# lora_internal_dev_board.net
KiCad netlist of a schematic drawn in EasyEDA
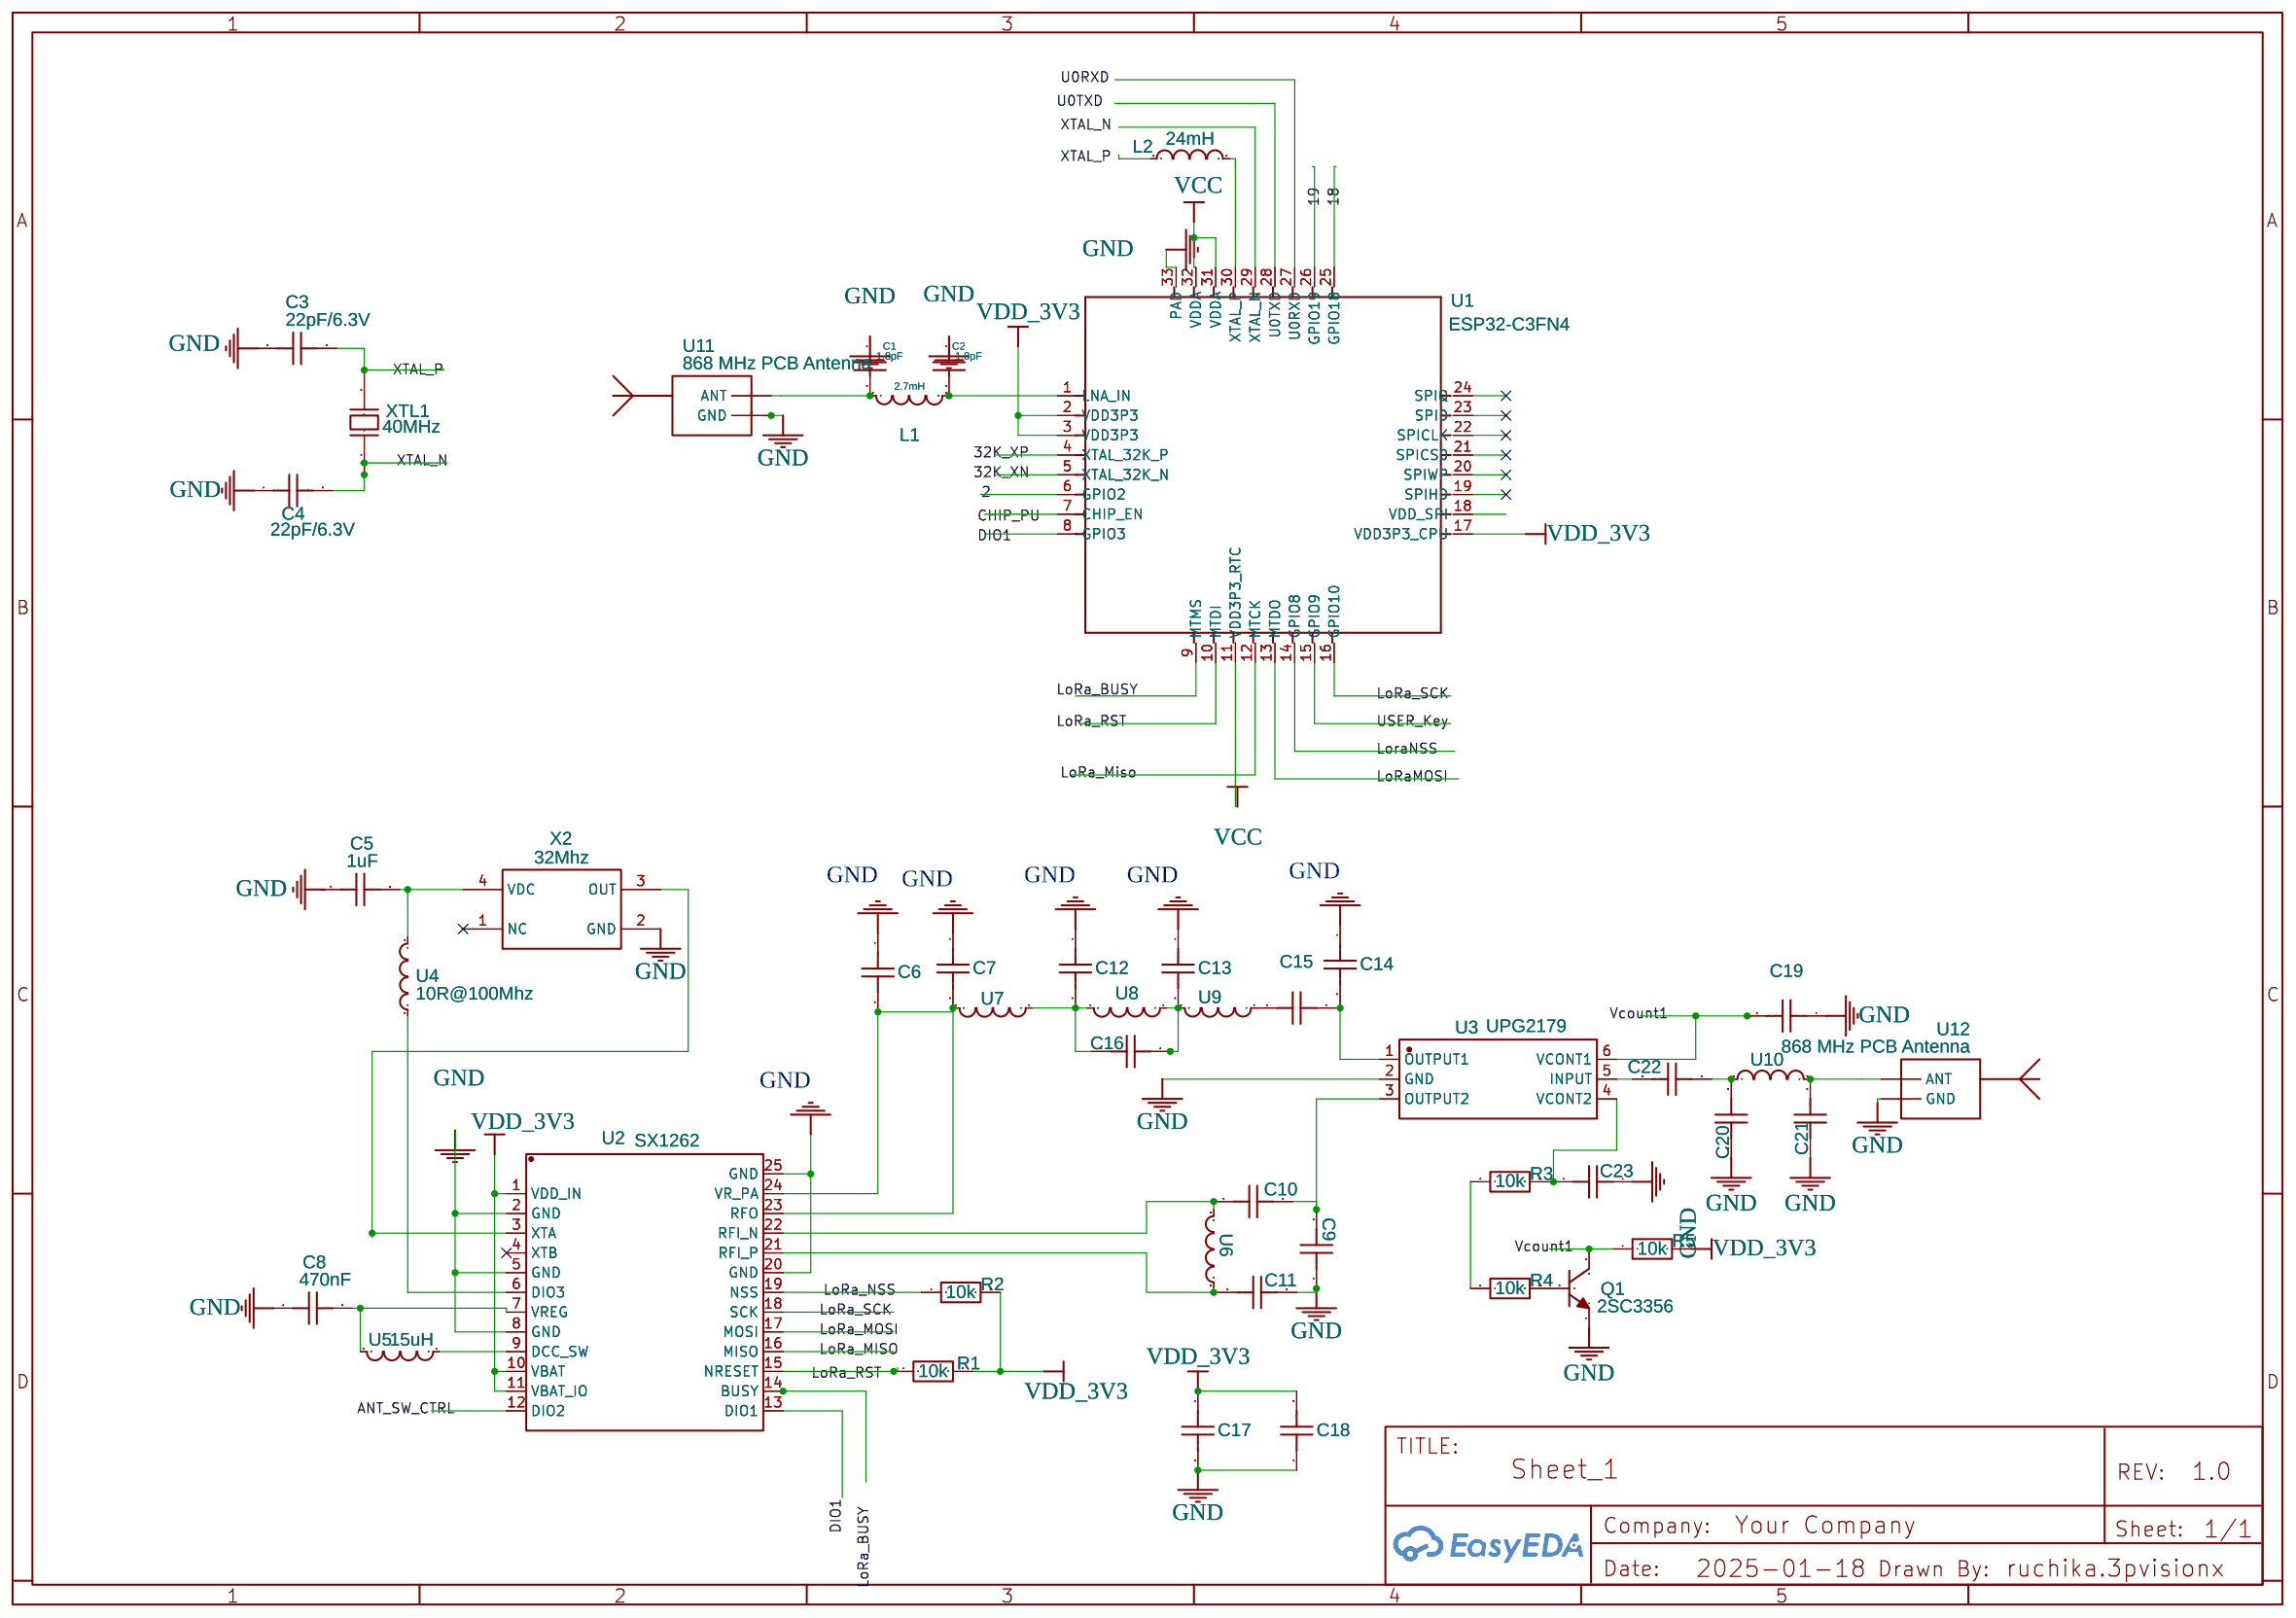
[diagram p0: schematic sheet]

(export (version "E")
  (design (tool "Eeschema 10.0.6"))
  (components
    (comp (ref "C1")
      (value "1.8pF")
      (fields
        (field (name "Manufacturer Part") "GJM1555C1H1R8BB01D")
        (field (name "Manufacturer") "muRata(村田)")
      )
      (libsource (lib "") (part "GJM1555C1H1R8BB01D"))
    )
    (comp (ref "C2")
      (value "1.8pF")
      (fields
        (field (name "Manufacturer Part") "GJM1555C1H1R8BB01D")
        (field (name "Manufacturer") "muRata(村田)")
      )
      (libsource (lib "") (part "GJM1555C1H1R8BB01D"))
    )
    (comp (ref "C3")
      (value "22pF/6.3V")
      (fields (field (name "Manufacturer Part") "22pF/6.3V(10%)-0402"))
      (libsource (lib "") (part "22PF/6.3V(10%)-0402"))
    )
    (comp (ref "C4")
      (value "22pF/6.3V")
      (fields (field (name "Manufacturer Part") "22pF/6.3V(10%)-0402"))
      (libsource (lib "") (part "22PF/6.3V(10%)-0402"))
    )
    (comp (ref "C5")
      (value "1uF")
      (fields
        (field (name "Manufacturer Part") "1uf/250V/CBBCapacitor")
        (field (name "Manufacturer") "ReliaPro")
      )
      (libsource (lib "") (part "1uf/250V/CBBCapacitor_3"))
    )
    (comp (ref "C6")
      (value "1uF")
      (fields
        (field (name "Manufacturer Part") "1uf/250V/CBBCapacitor")
        (field (name "Manufacturer") "ReliaPro")
      )
      (libsource (lib "") (part "1uf/250V/CBBCapacitor"))
    )
    (comp (ref "C7")
      (value "1uF")
      (fields
        (field (name "Manufacturer Part") "1uf/250V/CBBCapacitor")
        (field (name "Manufacturer") "ReliaPro")
      )
      (libsource (lib "") (part "1uf/250V/CBBCapacitor"))
    )
    (comp (ref "C8")
      (value "470nF")
      (fields
        (field (name "Manufacturer Part") "1uf/250V/CBBCapacitor")
        (field (name "Manufacturer") "ReliaPro")
      )
      (libsource (lib "") (part "1uf/250V/CBBCapacitor_3"))
    )
    (comp (ref "C9")
      (value "1uF")
      (fields
        (field (name "Manufacturer Part") "1uf/250V/CBBCapacitor")
        (field (name "Manufacturer") "ReliaPro")
      )
      (libsource (lib "") (part "1uf/250V/CBBCapacitor_2"))
    )
    (comp (ref "C10")
      (value "1uF")
      (fields
        (field (name "Manufacturer Part") "1uf/250V/CBBCapacitor")
        (field (name "Manufacturer") "ReliaPro")
      )
      (libsource (lib "") (part "1uf/250V/CBBCapacitor_3"))
    )
    (comp (ref "C11")
      (value "1uF")
      (fields
        (field (name "Manufacturer Part") "1uf/250V/CBBCapacitor")
        (field (name "Manufacturer") "ReliaPro")
      )
      (libsource (lib "") (part "1uf/250V/CBBCapacitor_3"))
    )
    (comp (ref "C12")
      (value "1uF")
      (fields
        (field (name "Manufacturer Part") "1uf/250V/CBBCapacitor")
        (field (name "Manufacturer") "ReliaPro")
      )
      (libsource (lib "") (part "1uf/250V/CBBCapacitor"))
    )
    (comp (ref "C13")
      (value "1uF")
      (fields
        (field (name "Manufacturer Part") "1uf/250V/CBBCapacitor")
        (field (name "Manufacturer") "ReliaPro")
      )
      (libsource (lib "") (part "1uf/250V/CBBCapacitor"))
    )
    (comp (ref "C14")
      (value "1uF")
      (fields
        (field (name "Manufacturer Part") "1uf/250V/CBBCapacitor")
        (field (name "Manufacturer") "ReliaPro")
      )
      (libsource (lib "") (part "1uf/250V/CBBCapacitor"))
    )
    (comp (ref "C15")
      (value "1uF")
      (fields
        (field (name "Manufacturer Part") "1uf/250V/CBBCapacitor")
        (field (name "Manufacturer") "ReliaPro")
      )
      (libsource (lib "") (part "1uf/250V/CBBCapacitor_1"))
    )
    (comp (ref "C16")
      (value "1uF")
      (fields
        (field (name "Manufacturer Part") "1uf/250V/CBBCapacitor")
        (field (name "Manufacturer") "ReliaPro")
      )
      (libsource (lib "") (part "1uf/250V/CBBCapacitor_1"))
    )
    (comp (ref "C17")
      (value "1uF")
      (fields
        (field (name "Manufacturer Part") "1uf/250V/CBBCapacitor")
        (field (name "Manufacturer") "ReliaPro")
      )
      (libsource (lib "") (part "1uf/250V/CBBCapacitor"))
    )
    (comp (ref "C18")
      (value "1uF")
      (fields
        (field (name "Manufacturer Part") "1uf/250V/CBBCapacitor")
        (field (name "Manufacturer") "ReliaPro")
      )
      (libsource (lib "") (part "1uf/250V/CBBCapacitor_2"))
    )
    (comp (ref "C19")
      (value "1uF")
      (fields
        (field (name "Manufacturer Part") "1uf/250V/CBBCapacitor")
        (field (name "Manufacturer") "ReliaPro")
      )
      (libsource (lib "") (part "1uf/250V/CBBCapacitor_1"))
    )
    (comp (ref "C20")
      (value "1uF")
      (fields
        (field (name "Manufacturer Part") "1uf/250V/CBBCapacitor")
        (field (name "Manufacturer") "ReliaPro")
      )
      (libsource (lib "") (part "1uf/250V/CBBCapacitor_2"))
    )
    (comp (ref "C21")
      (value "1uF")
      (fields
        (field (name "Manufacturer Part") "1uf/250V/CBBCapacitor")
        (field (name "Manufacturer") "ReliaPro")
      )
      (libsource (lib "") (part "1uf/250V/CBBCapacitor_2"))
    )
    (comp (ref "C22")
      (value "1uF")
      (fields
        (field (name "Manufacturer Part") "1uf/250V/CBBCapacitor")
        (field (name "Manufacturer") "ReliaPro")
      )
      (libsource (lib "") (part "1uf/250V/CBBCapacitor_1"))
    )
    (comp (ref "C23")
      (value "1uF")
      (fields
        (field (name "Manufacturer Part") "1uf/250V/CBBCapacitor")
        (field (name "Manufacturer") "ReliaPro")
      )
      (libsource (lib "") (part "1uf/250V/CBBCapacitor_1"))
    )
    (comp (ref "L1") (value "2.7mH") (libsource (lib "") (part "2.7mH sb3m")))
    (comp (ref "L2")
      (value "24mH")
      (fields (field (name "Manufacturer") "ML"))
      (libsource (lib "") (part "Inductor TH"))
    )
    (comp (ref "Q1")
      (value "2SC3356")
      (fields (field (name "Manufacturer") "FOSAN(富信)"))
      (libsource (lib "") (part "2SC3356_C5119709"))
    )
    (comp (ref "R1")
      (value "10k")
      (fields (field (name "Manufacturer Part") "贴片电阻ChipResistors"))
      (libsource (lib "") (part "贴片电阻CHIPRESISTORS"))
    )
    (comp (ref "R2")
      (value "10k")
      (fields (field (name "Manufacturer Part") "贴片电阻ChipResistors"))
      (libsource (lib "") (part "贴片电阻CHIPRESISTORS"))
    )
    (comp (ref "R3")
      (value "10k")
      (fields (field (name "Manufacturer Part") "贴片电阻ChipResistors"))
      (libsource (lib "") (part "贴片电阻CHIPRESISTORS"))
    )
    (comp (ref "R4")
      (value "10k")
      (fields (field (name "Manufacturer Part") "贴片电阻ChipResistors"))
      (libsource (lib "") (part "贴片电阻CHIPRESISTORS"))
    )
    (comp (ref "R5")
      (value "10k")
      (fields (field (name "Manufacturer Part") "贴片电阻ChipResistors"))
      (libsource (lib "") (part "贴片电阻CHIPRESISTORS"))
    )
    (comp (ref "U1") (value "ESP32-C3FN4") (libsource (lib "") (part "ESP32-C3FN4")))
    (comp (ref "U2")
      (value "SX1262")
      (fields (field (name "Manufacturer Part") "SX1262IMLTRT") (field (name "Manufacturer") "SEMTECH"))
      (libsource (lib "") (part "SX1262IMLTRT"))
    )
    (comp (ref "U3")
      (value "UPG2179")
      (fields
        (field (name "Manufacturer Part") "UPG2179TB-E4-A")
        (field (name "Manufacturer") "RENESAS(瑞萨)/IDT")
      )
      (libsource (lib "") (part "UPG2179TB-E4-A"))
    )
    (comp (ref "U4")
      (value "10R@100Mhz")
      (fields (field (name "Manufacturer Part") "10uH-INDUCTOR-0603"))
      (libsource (lib "") (part "10UH-INDUCTOR-0603"))
    )
    (comp (ref "U5")
      (value "15uH")
      (fields (field (name "Manufacturer Part") "10uH-INDUCTOR-0603"))
      (libsource (lib "") (part "10UH-INDUCTOR-0603_3"))
    )
    (comp (ref "U6")
      (value "15uH")
      (fields (field (name "Manufacturer Part") "10uH-INDUCTOR-0603"))
      (libsource (lib "") (part "10UH-INDUCTOR-0603_2"))
    )
    (comp (ref "U7")
      (value "15uH")
      (fields (field (name "Manufacturer Part") "10uH-INDUCTOR-0603"))
      (libsource (lib "") (part "10UH-INDUCTOR-0603_5"))
    )
    (comp (ref "U8")
      (value "15uH")
      (fields (field (name "Manufacturer Part") "10uH-INDUCTOR-0603"))
      (libsource (lib "") (part "10UH-INDUCTOR-0603_5"))
    )
    (comp (ref "U9")
      (value "15uH")
      (fields (field (name "Manufacturer Part") "10uH-INDUCTOR-0603"))
      (libsource (lib "") (part "10UH-INDUCTOR-0603_4"))
    )
    (comp (ref "U10")
      (value "15uH")
      (fields (field (name "Manufacturer Part") "10uH-INDUCTOR-0603"))
      (libsource (lib "") (part "10UH-INDUCTOR-0603_1"))
    )
    (comp (ref "U11") (value "868 MHz PCB Antenna") (libsource (lib "") (part "868 MHz PCB Antenna")))
    (comp (ref "U12") (value "868 MHz PCB Antenna") (libsource (lib "") (part "868 MHz PCB Antenna_1")))
    (comp (ref "X2")
      (value "32Mhz")
      (fields (field (name "Manufacturer") "YIC"))
      (libsource (lib "") (part "OSC40M-3.3/S5"))
    )
    (comp (ref "XTL1")
      (value "40MHz")
      (fields (field (name "Manufacturer Part") "NTPL INSIDE"))
      (libsource (lib "") (part "XTL - 16MHZ"))
    )
  )
  (nets
    (net (code "1") (name "/2") (class "Default")
      (node (ref "U1") (pin "6") (pinfunction "GPIO2_6") (pintype "unspecified"))
    )
    (net (code "9") (name "/LoRaMOSI") (class "Default")
      (node (ref "U1") (pin "13") (pinfunction "MTDO_13") (pintype "unspecified"))
    )
    (net (code "11") (name "/LoRa_MISO") (class "Default")
      (node (ref "U2") (pin "16") (pinfunction "MISO_16") (pintype "unspecified"))
    )
    (net (code "12") (name "/LoRa_MOSI") (class "Default")
      (node (ref "U2") (pin "17") (pinfunction "MOSI_17") (pintype "unspecified"))
    )
    (net (code "14") (name "/LoRa_NSS") (class "Default")
      (node (ref "R2") (pin "1") (pinfunction "1_1") (pintype "unspecified"))
      (node (ref "U2") (pin "19") (pinfunction "NSS_19") (pintype "unspecified"))
    )
    (net (code "16") (name "/LoRa_SCK") (class "Default")
      (node (ref "U1") (pin "16") (pinfunction "GPIO10_16") (pintype "unspecified"))
      (node (ref "U2") (pin "18") (pinfunction "SCK_18") (pintype "unspecified"))
    )
    (net (code "17") (name "/LoraNSS") (class "Default")
      (node (ref "U1") (pin "14") (pinfunction "GPIO8_14") (pintype "unspecified"))
    )
    (net (code "20") (name "/USER_Key") (class "Default")
      (node (ref "U1") (pin "15") (pinfunction "GPIO9_15") (pintype "unspecified"))
    )
    (net (code "22") (name "/XTAL_N") (class "Default")
      (node (ref "C4") (pin "2") (pinfunction "2_2") (pintype "unspecified"))
      (node (ref "XTL1") (pin "1") (pinfunction "1_1") (pintype "unspecified"))
    )
    (net (code "24") (name "GND") (class "Default")
      (node (ref "C1") (pin "1") (pinfunction "1_1") (pintype "input"))
      (node (ref "C11") (pin "2") (pinfunction "2_2") (pintype "unspecified"))
      (node (ref "C12") (pin "1") (pinfunction "1_1") (pintype "unspecified"))
      (node (ref "C13") (pin "1") (pinfunction "1_1") (pintype "unspecified"))
      (node (ref "C14") (pin "1") (pinfunction "1_1") (pintype "unspecified"))
      (node (ref "C17") (pin "2") (pinfunction "2_2") (pintype "unspecified"))
      (node (ref "C18") (pin "1") (pinfunction "1_1") (pintype "unspecified"))
      (node (ref "C19") (pin "1") (pinfunction "1_1") (pintype "unspecified"))
      (node (ref "C2") (pin "1") (pinfunction "1_1") (pintype "input"))
      (node (ref "C20") (pin "1") (pinfunction "1_1") (pintype "unspecified"))
      (node (ref "C21") (pin "1") (pinfunction "1_1") (pintype "unspecified"))
      (node (ref "C23") (pin "1") (pinfunction "1_1") (pintype "unspecified"))
      (node (ref "C3") (pin "1") (pinfunction "1_1") (pintype "unspecified"))
      (node (ref "C4") (pin "1") (pinfunction "1_1") (pintype "unspecified"))
      (node (ref "C6") (pin "1") (pinfunction "1_1") (pintype "unspecified"))
      (node (ref "C8") (pin "1") (pinfunction "1_1") (pintype "unspecified"))
      (node (ref "C9") (pin "1") (pinfunction "1_1") (pintype "unspecified"))
      (node (ref "Q1") (pin "1") (pinfunction "E_1") (pintype "input"))
      (node (ref "U1") (pin "33") (pinfunction "PAD_33") (pintype "unspecified"))
      (node (ref "U11") (pin "GND") (pinfunction "GND_GND") (pintype "unspecified"))
      (node (ref "U12") (pin "GND") (pinfunction "GND_GND") (pintype "unspecified"))
      (node (ref "U2") (pin "2") (pinfunction "GND_2") (pintype "unspecified"))
      (node (ref "U2") (pin "20") (pinfunction "GND_20") (pintype "unspecified"))
      (node (ref "U2") (pin "25") (pinfunction "GND_25") (pintype "unspecified"))
      (node (ref "U2") (pin "5") (pinfunction "GND_5") (pintype "unspecified"))
      (node (ref "U2") (pin "8") (pinfunction "GND_8") (pintype "unspecified"))
      (node (ref "U3") (pin "2") (pinfunction "GND_2") (pintype "unspecified"))
      (node (ref "X2") (pin "2") (pinfunction "GND_2") (pintype "unspecified"))
    )
    (net (code "25") (name "Net-(C1-Pad2)") (class "Default")
      (node (ref "C1") (pin "2") (pinfunction "2_2") (pintype "input"))
      (node (ref "L1") (pin "1") (pinfunction "1_1") (pintype "unspecified"))
      (node (ref "U11") (pin "ANT") (pinfunction "ANT_ANT") (pintype "unspecified"))
    )
    (net (code "26") (name "Net-(C3-Pad2)") (class "Default")
      (node (ref "C3") (pin "2") (pinfunction "2_2") (pintype "unspecified"))
      (node (ref "XTL1") (pin "2") (pinfunction "2_2") (pintype "unspecified"))
    )
    (net (code "27") (name "Net-(C12-Pad2)") (class "Default")
      (node (ref "C12") (pin "2") (pinfunction "2_2") (pintype "unspecified"))
      (node (ref "C16") (pin "2") (pinfunction "2_2") (pintype "unspecified"))
      (node (ref "U7") (pin "1") (pinfunction "1_1") (pintype "unspecified"))
      (node (ref "U8") (pin "2") (pinfunction "2_2") (pintype "unspecified"))
    )
    (net (code "28") (name "Net-(C13-Pad2)") (class "Default")
      (node (ref "C13") (pin "2") (pinfunction "2_2") (pintype "unspecified"))
      (node (ref "C16") (pin "1") (pinfunction "1_1") (pintype "unspecified"))
      (node (ref "U8") (pin "1") (pinfunction "1_1") (pintype "unspecified"))
      (node (ref "U9") (pin "2") (pinfunction "2_2") (pintype "unspecified"))
    )
    (net (code "29") (name "Net-(C15-Pad2)") (class "Default")
      (node (ref "C15") (pin "2") (pinfunction "2_2") (pintype "unspecified"))
      (node (ref "U9") (pin "1") (pinfunction "1_1") (pintype "unspecified"))
    )
    (net (code "30") (name "Net-(C20-Pad2)") (class "Default")
      (node (ref "C20") (pin "2") (pinfunction "2_2") (pintype "unspecified"))
      (node (ref "C22") (pin "1") (pinfunction "1_1") (pintype "unspecified"))
      (node (ref "U10") (pin "1") (pinfunction "1_1") (pintype "unspecified"))
    )
    (net (code "31") (name "Net-(C21-Pad2)") (class "Default")
      (node (ref "C21") (pin "2") (pinfunction "2_2") (pintype "unspecified"))
      (node (ref "U10") (pin "2") (pinfunction "2_2") (pintype "unspecified"))
      (node (ref "U12") (pin "ANT") (pinfunction "ANT_ANT") (pintype "unspecified"))
    )
    (net (code "32") (name "Net-(Q1-B)") (class "Default")
      (node (ref "Q1") (pin "2") (pinfunction "B_2") (pintype "input"))
      (node (ref "R4") (pin "2") (pinfunction "2_2") (pintype "unspecified"))
    )
    (net (code "33") (name "Net-(Q1-C)") (class "Default")
      (node (ref "Q1") (pin "3") (pinfunction "C_3") (pintype "input"))
      (node (ref "R5") (pin "1") (pinfunction "1_1") (pintype "unspecified"))
    )
    (net (code "34") (name "Net-(R3-Pad1)") (class "Default")
      (node (ref "R3") (pin "1") (pinfunction "1_1") (pintype "unspecified"))
      (node (ref "R4") (pin "1") (pinfunction "1_1") (pintype "unspecified"))
    )
    (net (code "35") (name "Net-(U1-LNA_IN)") (class "Default")
      (node (ref "C2") (pin "2") (pinfunction "2_2") (pintype "input"))
      (node (ref "L1") (pin "2") (pinfunction "2_2") (pintype "unspecified"))
      (node (ref "U1") (pin "1") (pinfunction "LNA_IN_1") (pintype "unspecified"))
    )
    (net (code "36") (name "Net-(U1-XTAL_P)") (class "Default")
      (node (ref "L2") (pin "2") (pinfunction "2_2") (pintype "unspecified"))
      (node (ref "U1") (pin "30") (pinfunction "XTAL_P_30") (pintype "unspecified"))
    )
    (net (code "37") (name "Net-(U2-DCC_SW)") (class "Default")
      (node (ref "U2") (pin "9") (pinfunction "DCC_SW_9") (pintype "unspecified"))
      (node (ref "U5") (pin "1") (pinfunction "1_1") (pintype "unspecified"))
    )
    (net (code "38") (name "Net-(U2-DIO3)") (class "Default")
      (node (ref "U2") (pin "6") (pinfunction "DIO3_6") (pintype "unspecified"))
      (node (ref "U4") (pin "1") (pinfunction "1_1") (pintype "unspecified"))
    )
    (net (code "39") (name "Net-(U2-NRESET)") (class "Default")
      (node (ref "R1") (pin "1") (pinfunction "1_1") (pintype "unspecified"))
      (node (ref "U2") (pin "15") (pinfunction "NRESET_15") (pintype "unspecified"))
    )
    (net (code "40") (name "Net-(U2-RFI_N)") (class "Default")
      (node (ref "C10") (pin "1") (pinfunction "1_1") (pintype "unspecified"))
      (node (ref "U2") (pin "22") (pinfunction "RFI_N_22") (pintype "unspecified"))
      (node (ref "U6") (pin "2") (pinfunction "2_2") (pintype "unspecified"))
    )
    (net (code "41") (name "Net-(U2-RFI_P)") (class "Default")
      (node (ref "C11") (pin "1") (pinfunction "1_1") (pintype "unspecified"))
      (node (ref "U2") (pin "21") (pinfunction "RFI_P_21") (pintype "unspecified"))
      (node (ref "U6") (pin "1") (pinfunction "1_1") (pintype "unspecified"))
    )
    (net (code "42") (name "Net-(U2-RFO)") (class "Default")
      (node (ref "C6") (pin "2") (pinfunction "2_2") (pintype "unspecified"))
      (node (ref "C7") (pin "2") (pinfunction "2_2") (pintype "unspecified"))
      (node (ref "U2") (pin "23") (pinfunction "RFO_23") (pintype "unspecified"))
      (node (ref "U2") (pin "24") (pinfunction "VR_PA_24") (pintype "unspecified"))
      (node (ref "U7") (pin "2") (pinfunction "2_2") (pintype "unspecified"))
    )
    (net (code "43") (name "Net-(U2-VREG)") (class "Default")
      (node (ref "C8") (pin "2") (pinfunction "2_2") (pintype "unspecified"))
      (node (ref "U2") (pin "7") (pinfunction "VREG_7") (pintype "unspecified"))
      (node (ref "U5") (pin "2") (pinfunction "2_2") (pintype "unspecified"))
    )
    (net (code "44") (name "Net-(U2-XTA)") (class "Default")
      (node (ref "U2") (pin "3") (pinfunction "XTA_3") (pintype "unspecified"))
      (node (ref "X2") (pin "3") (pinfunction "OUT_3") (pintype "unspecified"))
    )
    (net (code "45") (name "Net-(U3-INPUT)") (class "Default")
      (node (ref "C22") (pin "2") (pinfunction "2_2") (pintype "unspecified"))
      (node (ref "U3") (pin "5") (pinfunction "INPUT_5") (pintype "unspecified"))
    )
    (net (code "46") (name "Net-(U3-OUTPUT1)") (class "Default")
      (node (ref "C14") (pin "2") (pinfunction "2_2") (pintype "unspecified"))
      (node (ref "C15") (pin "1") (pinfunction "1_1") (pintype "unspecified"))
      (node (ref "U3") (pin "1") (pinfunction "OUTPUT1_1") (pintype "unspecified"))
    )
    (net (code "47") (name "Net-(U3-OUTPUT2)") (class "Default")
      (node (ref "C10") (pin "2") (pinfunction "2_2") (pintype "unspecified"))
      (node (ref "C9") (pin "2") (pinfunction "2_2") (pintype "unspecified"))
      (node (ref "U3") (pin "3") (pinfunction "OUTPUT2_3") (pintype "unspecified"))
    )
    (net (code "48") (name "Net-(U3-VCONT1)") (class "Default")
      (node (ref "C19") (pin "2") (pinfunction "2_2") (pintype "unspecified"))
      (node (ref "U3") (pin "6") (pinfunction "VCONT1_6") (pintype "unspecified"))
    )
    (net (code "49") (name "Net-(U3-VCONT2)") (class "Default")
      (node (ref "C23") (pin "2") (pinfunction "2_2") (pintype "unspecified"))
      (node (ref "R3") (pin "2") (pinfunction "2_2") (pintype "unspecified"))
      (node (ref "U3") (pin "4") (pinfunction "VCONT2_4") (pintype "unspecified"))
    )
    (net (code "50") (name "Net-(X2-VDC)") (class "Default")
      (node (ref "C5") (pin "2") (pinfunction "2_2") (pintype "unspecified"))
      (node (ref "U4") (pin "2") (pinfunction "2_2") (pintype "unspecified"))
      (node (ref "X2") (pin "4") (pinfunction "VDC_4") (pintype "unspecified"))
    )
    (net (code "51") (name "VCC") (class "Default")
      (node (ref "U1") (pin "11") (pinfunction "VDD3P3_RTC_11") (pintype "unspecified"))
      (node (ref "U1") (pin "31") (pinfunction "VDDA_31") (pintype "unspecified"))
      (node (ref "U1") (pin "32") (pinfunction "VDDA_32") (pintype "unspecified"))
    )
    (net (code "52") (name "VDD_3V3") (class "Default")
      (node (ref "C17") (pin "1") (pinfunction "1_1") (pintype "unspecified"))
      (node (ref "C18") (pin "2") (pinfunction "2_2") (pintype "unspecified"))
      (node (ref "R1") (pin "2") (pinfunction "2_2") (pintype "unspecified"))
      (node (ref "R2") (pin "2") (pinfunction "2_2") (pintype "unspecified"))
      (node (ref "R5") (pin "2") (pinfunction "2_2") (pintype "unspecified"))
      (node (ref "U1") (pin "17") (pinfunction "VDD3P3_CPU_17") (pintype "unspecified"))
      (node (ref "U1") (pin "2") (pinfunction "VDD3P3_2") (pintype "unspecified"))
      (node (ref "U1") (pin "3") (pinfunction "VDD3P3_3") (pintype "unspecified"))
      (node (ref "U2") (pin "1") (pinfunction "VDD_IN_1") (pintype "unspecified"))
      (node (ref "U2") (pin "10") (pinfunction "VBAT_10") (pintype "unspecified"))
      (node (ref "U2") (pin "11") (pinfunction "VBAT_IO_11") (pintype "unspecified"))
    )
    (net (code "53") (name "unconnected-(C5-Pad1)") (class "Default")
      (node (ref "C5") (pin "1") (pinfunction "1_1") (pintype "unspecified"))
    )
    (net (code "54") (name "unconnected-(C7-Pad1)") (class "Default")
      (node (ref "C7") (pin "1") (pinfunction "1_1") (pintype "unspecified"))
    )
    (net (code "55") (name "unconnected-(L2-Pad1)") (class "Default")
      (node (ref "L2") (pin "1") (pinfunction "1_1") (pintype "unspecified"))
    )
    (net (code "56") (name "unconnected-(U1-CHIP_EN-Pad7)") (class "Default")
      (node (ref "U1") (pin "7") (pinfunction "CHIP_EN_7") (pintype "unspecified"))
    )
    (net (code "57") (name "unconnected-(U1-GPIO3-Pad8)") (class "Default")
      (node (ref "U1") (pin "8") (pinfunction "GPIO3_8") (pintype "unspecified"))
    )
    (net (code "58") (name "unconnected-(U1-GPIO18-Pad25)") (class "Default")
      (node (ref "U1") (pin "25") (pinfunction "GPIO18_25") (pintype "unspecified"))
    )
    (net (code "59") (name "unconnected-(U1-GPIO19-Pad26)") (class "Default")
      (node (ref "U1") (pin "26") (pinfunction "GPIO19_26") (pintype "unspecified"))
    )
    (net (code "60") (name "unconnected-(U1-MTCK-Pad12)") (class "Default")
      (node (ref "U1") (pin "12") (pinfunction "MTCK_12") (pintype "unspecified"))
    )
    (net (code "61") (name "unconnected-(U1-MTDI-Pad10)") (class "Default")
      (node (ref "U1") (pin "10") (pinfunction "MTDI_10") (pintype "unspecified"))
    )
    (net (code "62") (name "unconnected-(U1-MTMS-Pad9)") (class "Default")
      (node (ref "U1") (pin "9") (pinfunction "MTMS_9") (pintype "unspecified"))
    )
    (net (code "63") (name "unconnected-(U1-SPICLK-Pad22)") (class "Default")
      (node (ref "U1") (pin "22") (pinfunction "SPICLK_22") (pintype "unspecified+no_connect"))
    )
    (net (code "64") (name "unconnected-(U1-SPICS0-Pad21)") (class "Default")
      (node (ref "U1") (pin "21") (pinfunction "SPICS0_21") (pintype "unspecified+no_connect"))
    )
    (net (code "65") (name "unconnected-(U1-SPID-Pad23)") (class "Default")
      (node (ref "U1") (pin "23") (pinfunction "SPID_23") (pintype "unspecified+no_connect"))
    )
    (net (code "66") (name "unconnected-(U1-SPIHD-Pad19)") (class "Default")
      (node (ref "U1") (pin "19") (pinfunction "SPIHD_19") (pintype "unspecified+no_connect"))
    )
    (net (code "67") (name "unconnected-(U1-SPIQ-Pad24)") (class "Default")
      (node (ref "U1") (pin "24") (pinfunction "SPIQ_24") (pintype "unspecified+no_connect"))
    )
    (net (code "68") (name "unconnected-(U1-SPIWP-Pad20)") (class "Default")
      (node (ref "U1") (pin "20") (pinfunction "SPIWP_20") (pintype "unspecified+no_connect"))
    )
    (net (code "69") (name "unconnected-(U1-U0RXD-Pad27)") (class "Default")
      (node (ref "U1") (pin "27") (pinfunction "U0RXD_27") (pintype "unspecified"))
    )
    (net (code "70") (name "unconnected-(U1-U0TXD-Pad28)") (class "Default")
      (node (ref "U1") (pin "28") (pinfunction "U0TXD_28") (pintype "unspecified"))
    )
    (net (code "71") (name "unconnected-(U1-VDD_SPI-Pad18)") (class "Default")
      (node (ref "U1") (pin "18") (pinfunction "VDD_SPI_18") (pintype "unspecified"))
    )
    (net (code "72") (name "unconnected-(U1-XTAL_32K_N-Pad5)") (class "Default")
      (node (ref "U1") (pin "5") (pinfunction "XTAL_32K_N_5") (pintype "unspecified"))
    )
    (net (code "73") (name "unconnected-(U1-XTAL_32K_P-Pad4)") (class "Default")
      (node (ref "U1") (pin "4") (pinfunction "XTAL_32K_P_4") (pintype "unspecified"))
    )
    (net (code "74") (name "unconnected-(U1-XTAL_N-Pad29)") (class "Default")
      (node (ref "U1") (pin "29") (pinfunction "XTAL_N_29") (pintype "unspecified"))
    )
    (net (code "75") (name "unconnected-(U2-BUSY-Pad14)") (class "Default")
      (node (ref "U2") (pin "14") (pinfunction "BUSY_14") (pintype "unspecified"))
    )
    (net (code "76") (name "unconnected-(U2-DIO1-Pad13)") (class "Default")
      (node (ref "U2") (pin "13") (pinfunction "DIO1_13") (pintype "unspecified"))
    )
    (net (code "77") (name "unconnected-(U2-DIO2-Pad12)") (class "Default")
      (node (ref "U2") (pin "12") (pinfunction "DIO2_12") (pintype "unspecified"))
    )
    (net (code "78") (name "unconnected-(U2-XTB-Pad4)") (class "Default")
      (node (ref "U2") (pin "4") (pinfunction "XTB_4") (pintype "unspecified+no_connect"))
    )
    (net (code "79") (name "unconnected-(X2-NC-Pad1)") (class "Default")
      (node (ref "X2") (pin "1") (pinfunction "NC_1") (pintype "unspecified+no_connect"))
    )
  )
)
